# ESP32_WROOM_Testboard.net
KiCad netlist of a schematic drawn in EAGLE
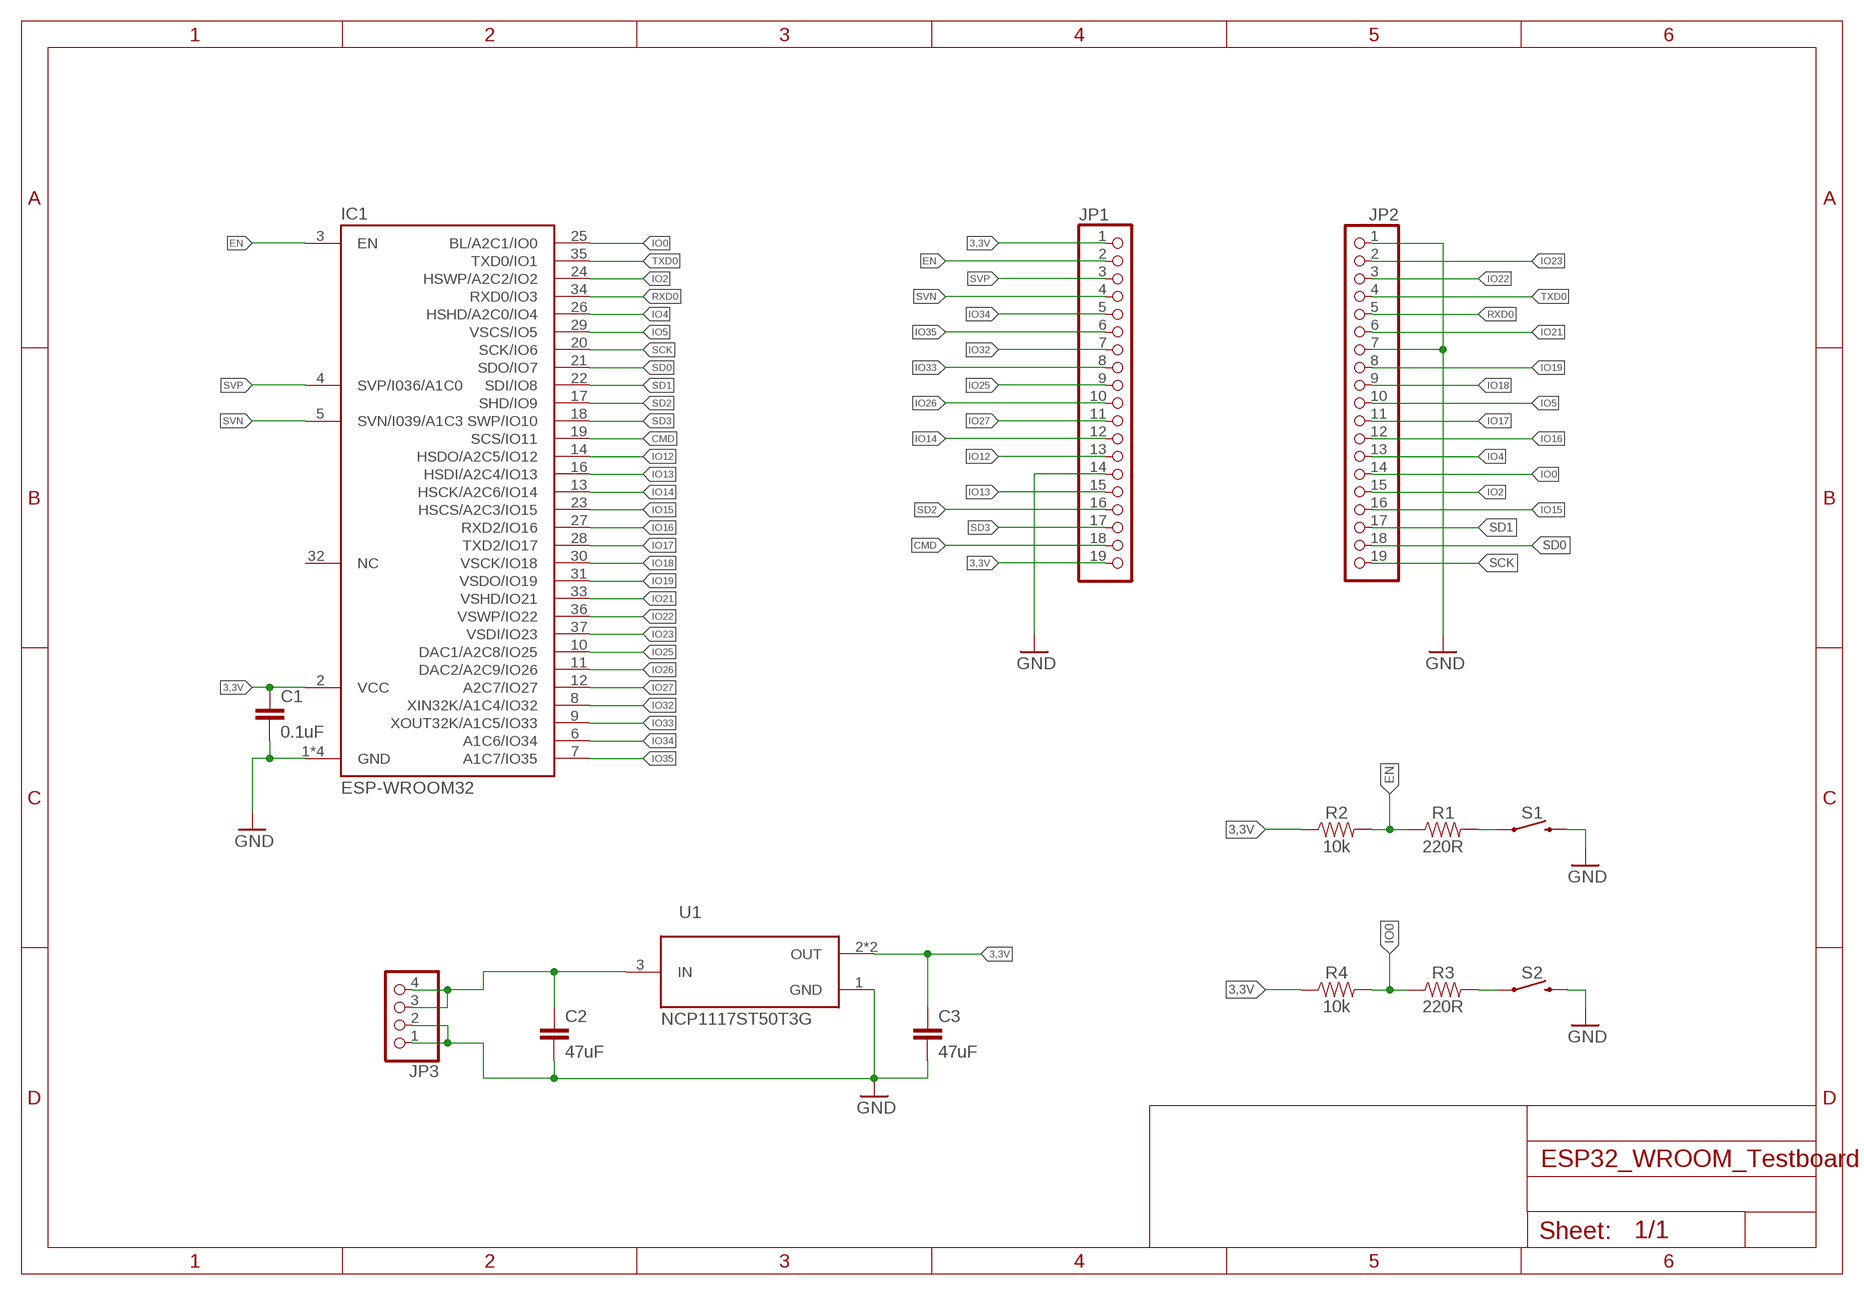
[diagram p0: schematic, sheet 1]

(export (version "E")
  (design (tool "Eeschema 10.0.6"))
  (components
    (comp (ref "C1")
      (value "0.1uF")
      (footprint "eagle-import:0603")
      (libsource (lib "eagle-import") (part "0.1UF-0603-25V-(+80/-20%)"))
    )
    (comp (ref "C2")
      (value "47uF")
      (footprint "eagle-import:0603")
      (libsource (lib "eagle-import") (part "0.1UF-0603-25V-(+80/-20%)"))
    )
    (comp (ref "C3")
      (value "47uF")
      (footprint "eagle-import:0603")
      (libsource (lib "eagle-import") (part "0.1UF-0603-25V-(+80/-20%)"))
    )
    (comp (ref "IC1")
      (value "ESP-WROOM32")
      (footprint "eagle-import:ESP-WROOM32")
      (libsource (lib "eagle-import") (part "ESP-WROOM32"))
    )
    (comp (ref "JP1")
      (value "PINHD-1X19")
      (footprint "eagle-import:1X19")
      (libsource (lib "eagle-import") (part "PINHD-1X19"))
    )
    (comp (ref "JP2")
      (value "PINHD-1X19")
      (footprint "eagle-import:1X19")
      (libsource (lib "eagle-import") (part "PINHD-1X19"))
    )
    (comp (ref "JP3")
      (value "PINHD-1X4")
      (footprint "eagle-import:1X04")
      (libsource (lib "eagle-import") (part "PINHD-1X4"))
    )
    (comp (ref "R1")
      (value "220R")
      (footprint "eagle-import:0805")
      (libsource (lib "eagle-import") (part "0.3OHM-0805-1/8W-1%"))
    )
    (comp (ref "R2")
      (value "10k")
      (footprint "eagle-import:0805")
      (libsource (lib "eagle-import") (part "0.3OHM-0805-1/8W-1%"))
    )
    (comp (ref "R3")
      (value "220R")
      (footprint "eagle-import:0805")
      (libsource (lib "eagle-import") (part "0.3OHM-0805-1/8W-1%"))
    )
    (comp (ref "R4")
      (value "10k")
      (footprint "eagle-import:0805")
      (libsource (lib "eagle-import") (part "0.3OHM-0805-1/8W-1%"))
    )
    (comp (ref "S1")
      (value "MOMENTARY-SWITCH-SPST-SMD-5.2-REDUNDANT")
      (footprint "eagle-import:TACTILE_SWITCH_SMD_5.2MM")
      (libsource (lib "eagle-import") (part "MOMENTARY-SWITCH-SPST-SMD-5.2-REDUNDANT"))
    )
    (comp (ref "S2")
      (value "MOMENTARY-SWITCH-SPST-SMD-5.2-REDUNDANT")
      (footprint "eagle-import:TACTILE_SWITCH_SMD_5.2MM")
      (libsource (lib "eagle-import") (part "MOMENTARY-SWITCH-SPST-SMD-5.2-REDUNDANT"))
    )
    (comp (ref "U1")
      (value "NCP1117ST50T3G")
      (footprint "eagle-import:SOT230P700X180-4N")
      (fields (field (name "MF") "ON Semiconductor"))
      (libsource (lib "eagle-import") (part "NCP1117ST50T3G"))
    )
  )
  (nets
    (net (code "1") (name "3,3V") (class "Default")
      (node (ref "C1") (pin "1") (pinfunction "1_1") (pintype "passive"))
      (node (ref "C3") (pin "1") (pinfunction "1_1") (pintype "passive"))
      (node (ref "IC1") (pin "2") (pinfunction "VCC_2") (pintype "power_in"))
      (node (ref "JP1") (pin "1") (pinfunction "1_1") (pintype "passive"))
      (node (ref "JP1") (pin "19") (pinfunction "19_19") (pintype "passive"))
      (node (ref "R2") (pin "1") (pinfunction "1_1") (pintype "passive"))
      (node (ref "R4") (pin "1") (pinfunction "1_1") (pintype "passive"))
      (node (ref "U1") (pin "2") (pinfunction "OUT_2") (pintype "output"))
      (node (ref "U1") (pin "4") (pinfunction "OUT_4") (pintype "output"))
    )
    (net (code "2") (name "CMD") (class "Default")
      (node (ref "IC1") (pin "19") (pinfunction "SCS/IO11_19") (pintype "bidirectional"))
      (node (ref "JP1") (pin "18") (pinfunction "18_18") (pintype "passive"))
    )
    (net (code "3") (name "EN") (class "Default")
      (node (ref "IC1") (pin "3") (pinfunction "EN_3") (pintype "bidirectional"))
      (node (ref "JP1") (pin "2") (pinfunction "2_2") (pintype "passive"))
      (node (ref "R1") (pin "1") (pinfunction "1_1") (pintype "passive"))
      (node (ref "R2") (pin "2") (pinfunction "2_2") (pintype "passive"))
    )
    (net (code "4") (name "GND") (class "Default")
      (node (ref "C1") (pin "2") (pinfunction "2_2") (pintype "passive"))
      (node (ref "C2") (pin "2") (pinfunction "2_2") (pintype "passive"))
      (node (ref "C3") (pin "2") (pinfunction "2_2") (pintype "passive"))
      (node (ref "IC1") (pin "1") (pinfunction "GND_1") (pintype "power_in"))
      (node (ref "IC1") (pin "15") (pinfunction "GND_15") (pintype "power_in"))
      (node (ref "IC1") (pin "38") (pinfunction "GND_38") (pintype "power_in"))
      (node (ref "IC1") (pin "TP") (pinfunction "GND_TP") (pintype "power_in"))
      (node (ref "JP1") (pin "14") (pinfunction "14_14") (pintype "passive"))
      (node (ref "JP2") (pin "1") (pinfunction "1_1") (pintype "passive"))
      (node (ref "JP2") (pin "7") (pinfunction "7_7") (pintype "passive"))
      (node (ref "JP3") (pin "1") (pinfunction "1_1") (pintype "passive"))
      (node (ref "JP3") (pin "2") (pinfunction "2_2") (pintype "passive"))
      (node (ref "S1") (pin "3") (pinfunction "2_3") (pintype "passive"))
      (node (ref "S1") (pin "4") (pinfunction "2_4") (pintype "passive"))
      (node (ref "S2") (pin "3") (pinfunction "2_3") (pintype "passive"))
      (node (ref "S2") (pin "4") (pinfunction "2_4") (pintype "passive"))
      (node (ref "U1") (pin "1") (pinfunction "GND_1") (pintype "power_in"))
    )
    (net (code "5") (name "IO0") (class "Default")
      (node (ref "IC1") (pin "25") (pinfunction "BL/A2C1/IO0_25") (pintype "bidirectional"))
      (node (ref "JP2") (pin "14") (pinfunction "14_14") (pintype "passive"))
      (node (ref "R3") (pin "1") (pinfunction "1_1") (pintype "passive"))
      (node (ref "R4") (pin "2") (pinfunction "2_2") (pintype "passive"))
    )
    (net (code "6") (name "IO2") (class "Default")
      (node (ref "IC1") (pin "24") (pinfunction "HSWP/A2C2/IO2_24") (pintype "bidirectional"))
      (node (ref "JP2") (pin "15") (pinfunction "15_15") (pintype "passive"))
    )
    (net (code "7") (name "IO4") (class "Default")
      (node (ref "IC1") (pin "26") (pinfunction "HSHD/A2C0/IO4_26") (pintype "bidirectional"))
      (node (ref "JP2") (pin "13") (pinfunction "13_13") (pintype "passive"))
    )
    (net (code "8") (name "IO5") (class "Default")
      (node (ref "IC1") (pin "29") (pinfunction "VSCS/IO5_29") (pintype "bidirectional"))
      (node (ref "JP2") (pin "10") (pinfunction "10_10") (pintype "passive"))
    )
    (net (code "9") (name "IO12") (class "Default")
      (node (ref "IC1") (pin "14") (pinfunction "HSDO/A2C5/IO12_14") (pintype "bidirectional"))
      (node (ref "JP1") (pin "13") (pinfunction "13_13") (pintype "passive"))
    )
    (net (code "10") (name "IO13") (class "Default")
      (node (ref "IC1") (pin "16") (pinfunction "HSDI/A2C4/IO13_16") (pintype "bidirectional"))
      (node (ref "JP1") (pin "15") (pinfunction "15_15") (pintype "passive"))
    )
    (net (code "11") (name "IO14") (class "Default")
      (node (ref "IC1") (pin "13") (pinfunction "HSCK/A2C6/IO14_13") (pintype "bidirectional"))
      (node (ref "JP1") (pin "12") (pinfunction "12_12") (pintype "passive"))
    )
    (net (code "12") (name "IO15") (class "Default")
      (node (ref "IC1") (pin "23") (pinfunction "HSCS/A2C3/IO15_23") (pintype "bidirectional"))
      (node (ref "JP2") (pin "16") (pinfunction "16_16") (pintype "passive"))
    )
    (net (code "13") (name "IO16") (class "Default")
      (node (ref "IC1") (pin "27") (pinfunction "RXD2/IO16_27") (pintype "bidirectional"))
      (node (ref "JP2") (pin "12") (pinfunction "12_12") (pintype "passive"))
    )
    (net (code "14") (name "IO17") (class "Default")
      (node (ref "IC1") (pin "28") (pinfunction "TXD2/IO17_28") (pintype "bidirectional"))
      (node (ref "JP2") (pin "11") (pinfunction "11_11") (pintype "passive"))
    )
    (net (code "15") (name "IO18") (class "Default")
      (node (ref "IC1") (pin "30") (pinfunction "VSCK/IO18_30") (pintype "bidirectional"))
      (node (ref "JP2") (pin "9") (pinfunction "9_9") (pintype "passive"))
    )
    (net (code "16") (name "IO19") (class "Default")
      (node (ref "IC1") (pin "31") (pinfunction "VSDO/IO19_31") (pintype "bidirectional"))
      (node (ref "JP2") (pin "8") (pinfunction "8_8") (pintype "passive"))
    )
    (net (code "17") (name "IO21") (class "Default")
      (node (ref "IC1") (pin "33") (pinfunction "VSHD/IO21_33") (pintype "bidirectional"))
      (node (ref "JP2") (pin "6") (pinfunction "6_6") (pintype "passive"))
    )
    (net (code "18") (name "IO22") (class "Default")
      (node (ref "IC1") (pin "36") (pinfunction "VSWP/IO22_36") (pintype "bidirectional"))
      (node (ref "JP2") (pin "3") (pinfunction "3_3") (pintype "passive"))
    )
    (net (code "19") (name "IO23") (class "Default")
      (node (ref "IC1") (pin "37") (pinfunction "VSDI/IO23_37") (pintype "bidirectional"))
      (node (ref "JP2") (pin "2") (pinfunction "2_2") (pintype "passive"))
    )
    (net (code "20") (name "IO25") (class "Default")
      (node (ref "IC1") (pin "10") (pinfunction "DAC1/A2C8/IO25_10") (pintype "bidirectional"))
      (node (ref "JP1") (pin "9") (pinfunction "9_9") (pintype "passive"))
    )
    (net (code "21") (name "IO26") (class "Default")
      (node (ref "IC1") (pin "11") (pinfunction "DAC2/A2C9/IO26_11") (pintype "bidirectional"))
      (node (ref "JP1") (pin "10") (pinfunction "10_10") (pintype "passive"))
    )
    (net (code "22") (name "IO27") (class "Default")
      (node (ref "IC1") (pin "12") (pinfunction "A2C7/IO27_12") (pintype "bidirectional"))
      (node (ref "JP1") (pin "11") (pinfunction "11_11") (pintype "passive"))
    )
    (net (code "23") (name "IO32") (class "Default")
      (node (ref "IC1") (pin "8") (pinfunction "XIN32K/A1C4/IO32_8") (pintype "bidirectional"))
      (node (ref "JP1") (pin "7") (pinfunction "7_7") (pintype "passive"))
    )
    (net (code "24") (name "IO33") (class "Default")
      (node (ref "IC1") (pin "9") (pinfunction "XOUT32K/A1C5/IO33_9") (pintype "bidirectional"))
      (node (ref "JP1") (pin "8") (pinfunction "8_8") (pintype "passive"))
    )
    (net (code "25") (name "IO34") (class "Default")
      (node (ref "IC1") (pin "6") (pinfunction "A1C6/IO34_6") (pintype "bidirectional"))
      (node (ref "JP1") (pin "5") (pinfunction "5_5") (pintype "passive"))
    )
    (net (code "26") (name "IO35") (class "Default")
      (node (ref "IC1") (pin "7") (pinfunction "A1C7/IO35_7") (pintype "bidirectional"))
      (node (ref "JP1") (pin "6") (pinfunction "6_6") (pintype "passive"))
    )
    (net (code "27") (name "Net-(R1-Pad2)") (class "Default")
      (node (ref "R1") (pin "2") (pinfunction "2_2") (pintype "passive"))
      (node (ref "S1") (pin "1") (pinfunction "1_1") (pintype "passive"))
      (node (ref "S1") (pin "2") (pinfunction "1_2") (pintype "passive"))
    )
    (net (code "28") (name "Net-(R3-Pad2)") (class "Default")
      (node (ref "R3") (pin "2") (pinfunction "2_2") (pintype "passive"))
      (node (ref "S2") (pin "1") (pinfunction "1_1") (pintype "passive"))
      (node (ref "S2") (pin "2") (pinfunction "1_2") (pintype "passive"))
    )
    (net (code "29") (name "Net-(U1-IN)") (class "Default")
      (node (ref "C2") (pin "1") (pinfunction "1_1") (pintype "passive"))
      (node (ref "JP3") (pin "3") (pinfunction "3_3") (pintype "passive"))
      (node (ref "JP3") (pin "4") (pinfunction "4_4") (pintype "passive"))
      (node (ref "U1") (pin "3") (pinfunction "IN_3") (pintype "input"))
    )
    (net (code "30") (name "RXD0") (class "Default")
      (node (ref "IC1") (pin "34") (pinfunction "RXD0/IO3_34") (pintype "bidirectional"))
      (node (ref "JP2") (pin "5") (pinfunction "5_5") (pintype "passive"))
    )
    (net (code "31") (name "SCK") (class "Default")
      (node (ref "IC1") (pin "20") (pinfunction "SCK/IO6_20") (pintype "bidirectional"))
      (node (ref "JP2") (pin "19") (pinfunction "19_19") (pintype "passive"))
    )
    (net (code "32") (name "SD0") (class "Default")
      (node (ref "IC1") (pin "21") (pinfunction "SDO/IO7_21") (pintype "bidirectional"))
      (node (ref "JP2") (pin "18") (pinfunction "18_18") (pintype "passive"))
    )
    (net (code "33") (name "SD1") (class "Default")
      (node (ref "IC1") (pin "22") (pinfunction "SDI/IO8_22") (pintype "bidirectional"))
      (node (ref "JP2") (pin "17") (pinfunction "17_17") (pintype "passive"))
    )
    (net (code "34") (name "SD2") (class "Default")
      (node (ref "IC1") (pin "17") (pinfunction "SHD/IO9_17") (pintype "bidirectional"))
      (node (ref "JP1") (pin "16") (pinfunction "16_16") (pintype "passive"))
    )
    (net (code "35") (name "SD3") (class "Default")
      (node (ref "IC1") (pin "18") (pinfunction "SWP/IO10_18") (pintype "bidirectional"))
      (node (ref "JP1") (pin "17") (pinfunction "17_17") (pintype "passive"))
    )
    (net (code "36") (name "SVN") (class "Default")
      (node (ref "IC1") (pin "5") (pinfunction "SVN/I039/A1C3_5") (pintype "bidirectional"))
      (node (ref "JP1") (pin "4") (pinfunction "4_4") (pintype "passive"))
    )
    (net (code "37") (name "SVP") (class "Default")
      (node (ref "IC1") (pin "4") (pinfunction "SVP/I036/A1C0_4") (pintype "bidirectional"))
      (node (ref "JP1") (pin "3") (pinfunction "3_3") (pintype "passive"))
    )
    (net (code "38") (name "TXD0") (class "Default")
      (node (ref "IC1") (pin "35") (pinfunction "TXD0/IO1_35") (pintype "bidirectional"))
      (node (ref "JP2") (pin "4") (pinfunction "4_4") (pintype "passive"))
    )
    (net (code "39") (name "unconnected-(IC1-NC-Pad32)") (class "Default")
      (node (ref "IC1") (pin "32") (pinfunction "NC_32") (pintype "bidirectional"))
    )
  )
)
